# VGA.net
KiCad netlist of a schematic drawn in Altium Designer
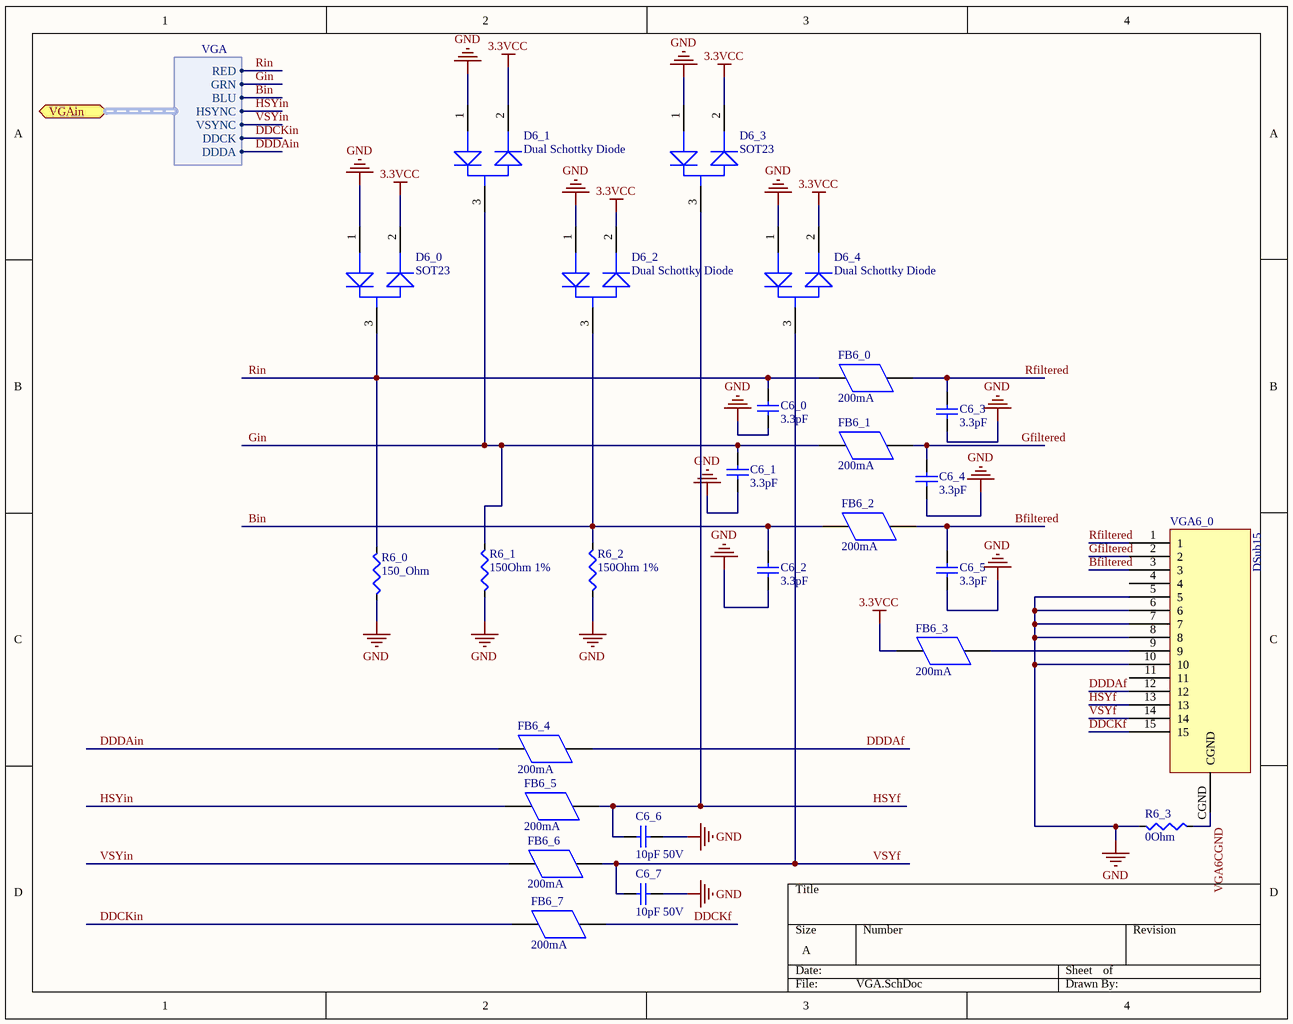
[diagram p0: VGA.SchDoc]

(export (version "E")
  (design (tool "Eeschema 10.0.6"))
  (components
    (comp (ref "C6_0")
      (value "3.3pF")
      (footprint "PassiveComponents:0805 (2012) Capacitor")
      (description "Capacitor")
      (libsource (lib "PassiveComponents") (part "Capacitor (non-polarized)"))
    )
    (comp (ref "C6_1")
      (value "3.3pF")
      (footprint "PassiveComponents:0805 (2012) Capacitor")
      (description "Capacitor")
      (libsource (lib "PassiveComponents") (part "Capacitor (non-polarized)"))
    )
    (comp (ref "C6_2")
      (value "3.3pF")
      (footprint "PassiveComponents:0805 (2012) Capacitor")
      (description "Capacitor")
      (libsource (lib "PassiveComponents") (part "Capacitor (non-polarized)"))
    )
    (comp (ref "C6_3")
      (value "3.3pF")
      (footprint "PassiveComponents:0805 (2012) Capacitor")
      (description "Capacitor")
      (libsource (lib "PassiveComponents") (part "Capacitor (non-polarized)"))
    )
    (comp (ref "C6_4")
      (value "3.3pF")
      (footprint "PassiveComponents:0805 (2012) Capacitor")
      (description "Capacitor")
      (libsource (lib "PassiveComponents") (part "Capacitor (non-polarized)"))
    )
    (comp (ref "C6_5")
      (value "3.3pF")
      (footprint "PassiveComponents:0805 (2012) Capacitor")
      (description "Capacitor")
      (libsource (lib "PassiveComponents") (part "Capacitor (non-polarized)"))
    )
    (comp (ref "C6_6")
      (value "10pF 50V")
      (footprint "PassiveComponents:0805 (2012) Capacitor")
      (description "Capacitor")
      (libsource (lib "PassiveComponents") (part "Capacitor (non-polarized)"))
    )
    (comp (ref "C6_7")
      (value "10pF 50V")
      (footprint "PassiveComponents:0805 (2012) Capacitor")
      (description "Capacitor")
      (libsource (lib "PassiveComponents") (part "Capacitor (non-polarized)"))
    )
    (comp (ref "D6_0")
      (value "SOT23")
      (footprint "PassiveComponents:SOT23")
      (description "Dual Schottky Diode")
      (libsource (lib "PassiveComponents") (part "Dual Schottky Diode"))
    )
    (comp (ref "D6_1")
      (value "Dual Schottky Diode")
      (footprint "PassiveComponents:SOT23")
      (libsource (lib "PassiveComponents") (part "Dual Schottky Diode"))
    )
    (comp (ref "D6_2")
      (value "Dual Schottky Diode")
      (footprint "PassiveComponents:SOT23")
      (libsource (lib "PassiveComponents") (part "Dual Schottky Diode"))
    )
    (comp (ref "D6_3")
      (value "SOT23")
      (footprint "PassiveComponents:SOT23")
      (description "Dual Schottky Diode")
      (libsource (lib "PassiveComponents") (part "Dual Schottky Diode"))
    )
    (comp (ref "D6_4")
      (value "Dual Schottky Diode")
      (footprint "PassiveComponents:SOT23")
      (libsource (lib "PassiveComponents") (part "Dual Schottky Diode"))
    )
    (comp (ref "FB6_0")
      (value "200mA")
      (footprint "PassiveComponents:0805 (2012) Capacitor")
      (description "Ferrite Beads")
      (libsource (lib "PassiveComponents") (part "Ferrite Beads"))
    )
    (comp (ref "FB6_1")
      (value "200mA")
      (footprint "PassiveComponents:0805 (2012) Capacitor")
      (description "Ferrite Beads")
      (libsource (lib "PassiveComponents") (part "Ferrite Beads"))
    )
    (comp (ref "FB6_2")
      (value "200mA")
      (footprint "PassiveComponents:0805 (2012) Capacitor")
      (description "Ferrite Beads")
      (libsource (lib "PassiveComponents") (part "Ferrite Beads"))
    )
    (comp (ref "FB6_3")
      (value "200mA")
      (footprint "PassiveComponents:0805 (2012) Capacitor")
      (description "Ferrite Beads")
      (libsource (lib "PassiveComponents") (part "Ferrite Beads"))
    )
    (comp (ref "FB6_4")
      (value "200mA")
      (footprint "PassiveComponents:0805 (2012) Capacitor")
      (description "Ferrite Beads")
      (libsource (lib "PassiveComponents") (part "Ferrite Beads"))
    )
    (comp (ref "FB6_5")
      (value "200mA")
      (footprint "PassiveComponents:0805 (2012) Capacitor")
      (description "Ferrite Beads")
      (libsource (lib "PassiveComponents") (part "Ferrite Beads"))
    )
    (comp (ref "FB6_6")
      (value "200mA")
      (footprint "PassiveComponents:0805 (2012) Capacitor")
      (description "Ferrite Beads")
      (libsource (lib "PassiveComponents") (part "Ferrite Beads"))
    )
    (comp (ref "FB6_7")
      (value "200mA")
      (footprint "PassiveComponents:0805 (2012) Capacitor")
      (description "Ferrite Beads")
      (libsource (lib "PassiveComponents") (part "Ferrite Beads"))
    )
    (comp (ref "R6_0")
      (value "150_Ohm")
      (footprint "PassiveComponents:R 0805 (2012) RESISTOR")
      (description "Resistor")
      (fields (field (name "DIGIKEY PART NUMBER") "RHM150CRCT-ND"))
      (libsource (lib "PassiveComponents") (part "Resistor"))
    )
    (comp (ref "R6_1")
      (value "150Ohm 1%")
      (footprint "PassiveComponents:R 0805 (2012) RESISTOR")
      (description "Resistor")
      (fields (field (name "DIGIKEY PART NUMBER") "RHM150CRCT-ND"))
      (libsource (lib "PassiveComponents") (part "Resistor"))
    )
    (comp (ref "R6_2")
      (value "150Ohm 1%")
      (footprint "PassiveComponents:R 0805 (2012) RESISTOR")
      (description "Resistor")
      (fields (field (name "DIGIKEY PART NUMBER") "RHM150CRCT-ND"))
      (libsource (lib "PassiveComponents") (part "Resistor"))
    )
    (comp (ref "R6_3")
      (value "0Ohm")
      (footprint "PassiveComponents:R 1210 (3225) RESISTOR")
      (description "Resistor")
      (libsource (lib "PassiveComponents") (part "Resistor"))
    )
    (comp (ref "VGA6_0")
      (value "DSub15")
      (footprint "DSubConnectors:DSub15")
      (description "DSub15 Connector Tyco PN 1734344")
      (libsource (lib "DSubConnectors") (part "DSub15"))
    )
  )
  (nets
    (net (code "2") (name "/Bfiltered") (class "Default")
      (node (ref "C6_5") (pin "1") (pinfunction "1_1") (pintype "passive"))
      (node (ref "FB6_2") (pin "2") (pinfunction "2_2") (pintype "passive"))
      (node (ref "VGA6_0") (pin "3") (pinfunction "3_3") (pintype "passive"))
    )
    (net (code "3") (name "/Bin") (class "Default")
      (node (ref "C6_2") (pin "1") (pinfunction "1_1") (pintype "passive"))
      (node (ref "D6_2") (pin "3") (pinfunction "3_3") (pintype "passive"))
      (node (ref "FB6_2") (pin "1") (pinfunction "1_1") (pintype "passive"))
      (node (ref "R6_2") (pin "2") (pinfunction "2_2") (pintype "passive"))
    )
    (net (code "4") (name "/DDCKf") (class "Default")
      (node (ref "FB6_7") (pin "2") (pinfunction "2_2") (pintype "passive"))
      (node (ref "VGA6_0") (pin "15") (pinfunction "15_15") (pintype "passive"))
    )
    (net (code "5") (name "/DDCKin") (class "Default")
      (node (ref "FB6_7") (pin "1") (pinfunction "1_1") (pintype "passive"))
    )
    (net (code "6") (name "/DDDAf") (class "Default")
      (node (ref "FB6_4") (pin "2") (pinfunction "2_2") (pintype "passive"))
      (node (ref "VGA6_0") (pin "12") (pinfunction "12_12") (pintype "passive"))
    )
    (net (code "7") (name "/DDDAin") (class "Default")
      (node (ref "FB6_4") (pin "1") (pinfunction "1_1") (pintype "passive"))
    )
    (net (code "8") (name "/Gfiltered") (class "Default")
      (node (ref "C6_4") (pin "1") (pinfunction "1_1") (pintype "passive"))
      (node (ref "FB6_1") (pin "2") (pinfunction "2_2") (pintype "passive"))
      (node (ref "VGA6_0") (pin "2") (pinfunction "2_2") (pintype "passive"))
    )
    (net (code "9") (name "/Gin") (class "Default")
      (node (ref "C6_1") (pin "1") (pinfunction "1_1") (pintype "passive"))
      (node (ref "D6_1") (pin "3") (pinfunction "3_3") (pintype "passive"))
      (node (ref "FB6_1") (pin "1") (pinfunction "1_1") (pintype "passive"))
      (node (ref "R6_1") (pin "2") (pinfunction "2_2") (pintype "passive"))
    )
    (net (code "10") (name "/HSYf") (class "Default")
      (node (ref "C6_6") (pin "2") (pinfunction "2_2") (pintype "passive"))
      (node (ref "D6_3") (pin "3") (pinfunction "3_3") (pintype "passive"))
      (node (ref "FB6_5") (pin "2") (pinfunction "2_2") (pintype "passive"))
      (node (ref "VGA6_0") (pin "13") (pinfunction "13_13") (pintype "passive"))
    )
    (net (code "11") (name "/HSYin") (class "Default")
      (node (ref "FB6_5") (pin "1") (pinfunction "1_1") (pintype "passive"))
    )
    (net (code "12") (name "/Rfiltered") (class "Default")
      (node (ref "C6_3") (pin "1") (pinfunction "1_1") (pintype "passive"))
      (node (ref "FB6_0") (pin "2") (pinfunction "2_2") (pintype "passive"))
      (node (ref "VGA6_0") (pin "1") (pinfunction "1_1") (pintype "passive"))
    )
    (net (code "13") (name "/Rin") (class "Default")
      (node (ref "C6_0") (pin "1") (pinfunction "1_1") (pintype "passive"))
      (node (ref "D6_0") (pin "3") (pinfunction "3_3") (pintype "passive"))
      (node (ref "FB6_0") (pin "1") (pinfunction "1_1") (pintype "passive"))
      (node (ref "R6_0") (pin "2") (pinfunction "2_2") (pintype "passive"))
    )
    (net (code "14") (name "/VGA6CGND") (class "Default")
      (node (ref "R6_3") (pin "2") (pinfunction "2_2") (pintype "passive"))
      (node (ref "VGA6_0") (pin "CGND") (pinfunction "CGND_CGND") (pintype "passive"))
    )
    (net (code "15") (name "/VSYf") (class "Default")
      (node (ref "C6_7") (pin "2") (pinfunction "2_2") (pintype "passive"))
      (node (ref "D6_4") (pin "3") (pinfunction "3_3") (pintype "passive"))
      (node (ref "FB6_6") (pin "2") (pinfunction "2_2") (pintype "passive"))
      (node (ref "VGA6_0") (pin "14") (pinfunction "14_14") (pintype "passive"))
    )
    (net (code "16") (name "/VSYin") (class "Default")
      (node (ref "FB6_6") (pin "1") (pinfunction "1_1") (pintype "passive"))
    )
    (net (code "18") (name "3.3VCC") (class "Default")
      (node (ref "D6_0") (pin "2") (pinfunction "2_2") (pintype "passive"))
      (node (ref "D6_1") (pin "2") (pinfunction "2_2") (pintype "passive"))
      (node (ref "D6_2") (pin "2") (pinfunction "2_2") (pintype "passive"))
      (node (ref "D6_3") (pin "2") (pinfunction "2_2") (pintype "passive"))
      (node (ref "D6_4") (pin "2") (pinfunction "2_2") (pintype "passive"))
      (node (ref "FB6_3") (pin "1") (pinfunction "1_1") (pintype "passive"))
    )
    (net (code "19") (name "GND") (class "Default")
      (node (ref "C6_0") (pin "2") (pinfunction "2_2") (pintype "passive"))
      (node (ref "C6_1") (pin "2") (pinfunction "2_2") (pintype "passive"))
      (node (ref "C6_2") (pin "2") (pinfunction "2_2") (pintype "passive"))
      (node (ref "C6_3") (pin "2") (pinfunction "2_2") (pintype "passive"))
      (node (ref "C6_4") (pin "2") (pinfunction "2_2") (pintype "passive"))
      (node (ref "C6_5") (pin "2") (pinfunction "2_2") (pintype "passive"))
      (node (ref "C6_6") (pin "1") (pinfunction "1_1") (pintype "passive"))
      (node (ref "C6_7") (pin "1") (pinfunction "1_1") (pintype "passive"))
      (node (ref "D6_0") (pin "1") (pinfunction "1_1") (pintype "passive"))
      (node (ref "D6_1") (pin "1") (pinfunction "1_1") (pintype "passive"))
      (node (ref "D6_2") (pin "1") (pinfunction "1_1") (pintype "passive"))
      (node (ref "D6_3") (pin "1") (pinfunction "1_1") (pintype "passive"))
      (node (ref "D6_4") (pin "1") (pinfunction "1_1") (pintype "passive"))
      (node (ref "R6_0") (pin "1") (pinfunction "1_1") (pintype "passive"))
      (node (ref "R6_1") (pin "1") (pinfunction "1_1") (pintype "passive"))
      (node (ref "R6_2") (pin "1") (pinfunction "1_1") (pintype "passive"))
      (node (ref "R6_3") (pin "1") (pinfunction "1_1") (pintype "passive"))
      (node (ref "VGA6_0") (pin "10") (pinfunction "10_10") (pintype "passive"))
      (node (ref "VGA6_0") (pin "5") (pinfunction "5_5") (pintype "passive"))
      (node (ref "VGA6_0") (pin "6") (pinfunction "6_6") (pintype "passive"))
      (node (ref "VGA6_0") (pin "7") (pinfunction "7_7") (pintype "passive"))
      (node (ref "VGA6_0") (pin "8") (pinfunction "8_8") (pintype "passive"))
    )
    (net (code "20") (name "Net-(FB6_3-Pad2)") (class "Default")
      (node (ref "FB6_3") (pin "2") (pinfunction "2_2") (pintype "passive"))
      (node (ref "VGA6_0") (pin "9") (pinfunction "9_9") (pintype "passive"))
    )
    (net (code "21") (name "unconnected-(VGA6_0-Pad4)") (class "Default")
      (node (ref "VGA6_0") (pin "4") (pinfunction "4_4") (pintype "passive"))
    )
    (net (code "22") (name "unconnected-(VGA6_0-Pad11)") (class "Default")
      (node (ref "VGA6_0") (pin "11") (pinfunction "11_11") (pintype "passive"))
    )
  )
)
